# PSU_SET_1V2.net
KiCad netlist of a schematic drawn in Altium Designer
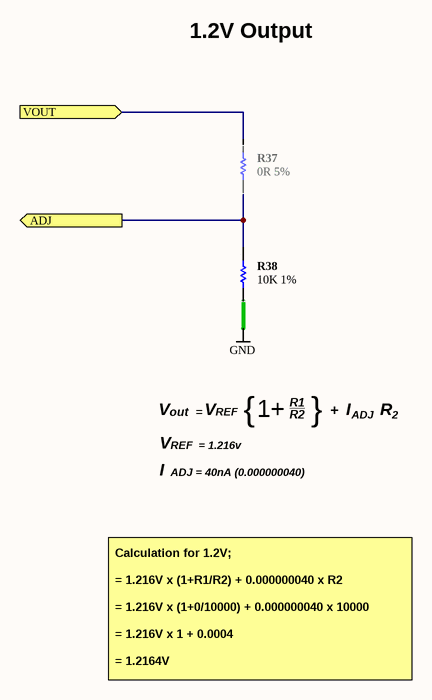
[diagram p0: PSU_SET_1V2.SchDoc]

(export (version "E")
  (design (tool "Eeschema 10.0.6"))
  (components
    (comp (ref "R37")
      (value "0R 5%")
      (footprint "RESC1005-STAR")
      (description "Resistor, 0R 5% 0402 (1005)")
      (fields (field (name "TOLERANCE") "5%"))
      (libsource (lib "AltiumDesignLibrary") (part "RES"))
    )
    (comp (ref "R38")
      (value "10K 1%")
      (footprint "RESC1005-STAR")
      (description "Resistor, 10K 1% 0402 (1005)")
      (fields (field (name "TOLERANCE") "1 %"))
      (libsource (lib "AltiumDesignLibrary") (part "RES"))
    )
  )
  (nets
    (net (code "1") (name "/ADJ") (class "Default")
      (node (ref "R37") (pin "1") (pinfunction "1_1") (pintype "passive"))
      (node (ref "R38") (pin "1") (pinfunction "1_1") (pintype "passive"))
    )
    (net (code "2") (name "/VOUT") (class "Default")
      (node (ref "R37") (pin "2") (pinfunction "2_2") (pintype "passive"))
    )
    (net (code "3") (name "GND") (class "Default")
      (node (ref "R38") (pin "2") (pinfunction "2_2") (pintype "passive"))
    )
  )
)
